# lab2_larionov_buck.net
KiCad netlist of a schematic drawn in Altium Designer
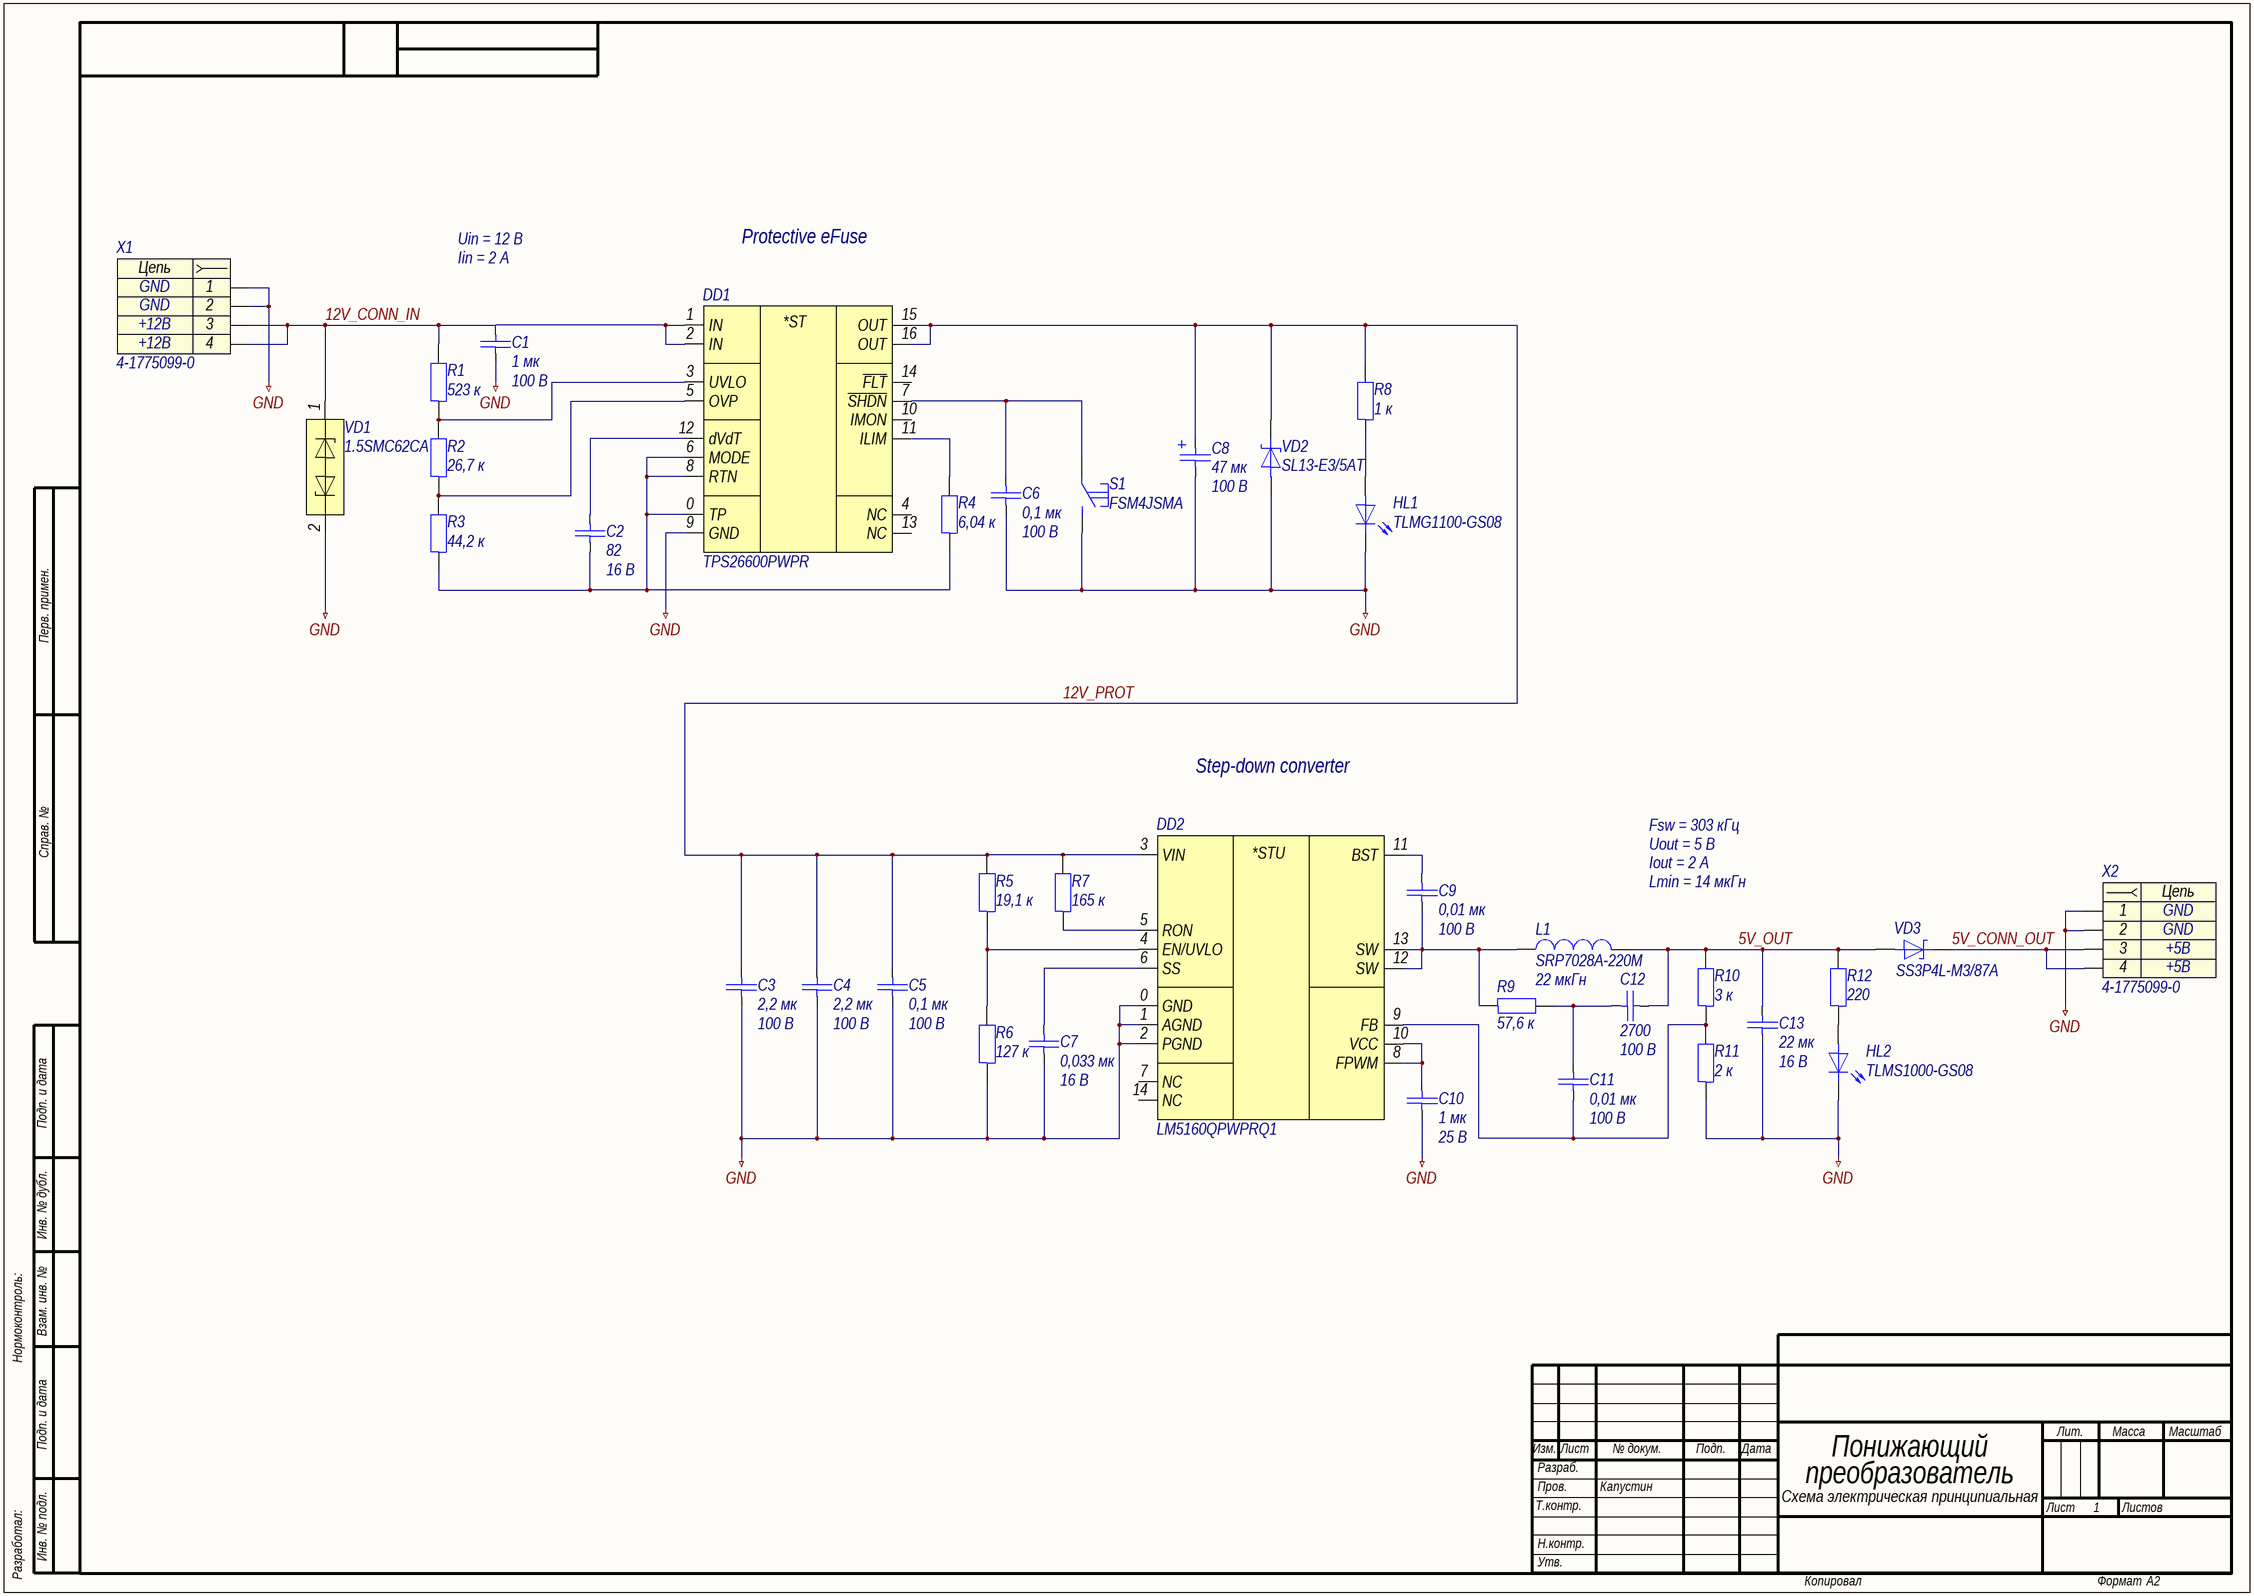
[diagram p0: lab2_larionov_buck.SchDoc]

(export (version "E")
  (design (tool "Eeschema 10.0.6"))
  (components
    (comp (ref "C1")
      (value "1 мк")
      (footprint "C1206")
      (description "=Описание")
      (fields (field (name "НАПРЯЖЕНИЕ") "100 В"))
      (libsource (lib "Database_Students") (part "C-NONPOLAR"))
    )
    (comp (ref "C2")
      (value "82")
      (footprint "C0603")
      (description "=Описание")
      (fields (field (name "НАПРЯЖЕНИЕ") "16 В"))
      (libsource (lib "Database_Students") (part "C-NONPOLAR"))
    )
    (comp (ref "C3")
      (value "2,2 мк")
      (footprint "C1206")
      (description "=Описание")
      (fields (field (name "НАПРЯЖЕНИЕ") "100 В"))
      (libsource (lib "Database_Students") (part "C-NONPOLAR"))
    )
    (comp (ref "C4")
      (value "2,2 мк")
      (footprint "C1206")
      (description "=Описание")
      (fields (field (name "НАПРЯЖЕНИЕ") "100 В"))
      (libsource (lib "Database_Students") (part "C-NONPOLAR"))
    )
    (comp (ref "C5")
      (value "0,1 мк")
      (footprint "C0603")
      (description "=Описание")
      (fields (field (name "НАПРЯЖЕНИЕ") "100 В"))
      (libsource (lib "Database_Students") (part "C-NONPOLAR"))
    )
    (comp (ref "C6")
      (value "0,1 мк")
      (footprint "C0603")
      (description "=Описание")
      (fields (field (name "НАПРЯЖЕНИЕ") "100 В"))
      (libsource (lib "Database_Students") (part "C-NONPOLAR"))
    )
    (comp (ref "C7")
      (value "0,033 мк")
      (footprint "C0603")
      (description "=Описание")
      (fields (field (name "НАПРЯЖЕНИЕ") "16 В"))
      (libsource (lib "Database_Students") (part "C-NONPOLAR"))
    )
    (comp (ref "C8")
      (value "47 мк")
      (footprint "CAPAE-1000X1000X1200")
      (description "=Описание")
      (fields (field (name "НАПРЯЖЕНИЕ") "100 В"))
      (libsource (lib "Database_Students") (part "C-POLAR"))
    )
    (comp (ref "C9")
      (value "0,01 мк")
      (footprint "C0603")
      (description "=Описание")
      (fields (field (name "НАПРЯЖЕНИЕ") "100 В"))
      (libsource (lib "Database_Students") (part "C-NONPOLAR"))
    )
    (comp (ref "C10")
      (value "1 мк")
      (footprint "C0603")
      (description "=Описание")
      (fields (field (name "НАПРЯЖЕНИЕ") "25 В"))
      (libsource (lib "Database_Students") (part "C-NONPOLAR"))
    )
    (comp (ref "C11")
      (value "0,01 мк")
      (footprint "C0603")
      (description "=Описание")
      (fields (field (name "НАПРЯЖЕНИЕ") "100 В"))
      (libsource (lib "Database_Students") (part "C-NONPOLAR"))
    )
    (comp (ref "C12")
      (value "2700")
      (footprint "C0603")
      (description "=Описание")
      (fields (field (name "НАПРЯЖЕНИЕ") "100 В"))
      (libsource (lib "Database_Students") (part "C-NONPOLAR"))
    )
    (comp (ref "C13")
      (value "22 мк")
      (footprint "C1206")
      (description "=Описание")
      (fields (field (name "НАПРЯЖЕНИЕ") "16 В"))
      (libsource (lib "Database_Students") (part "C-NONPOLAR"))
    )
    (comp (ref "DD1")
      (value "TPS26600PWPR")
      (footprint "HTSSOP-16")
      (description "=Описание")
      (libsource (lib "Database_Students") (part "TPS26600PWPR"))
    )
    (comp (ref "DD2")
      (value "LM5160QPWPRQ1")
      (footprint "HTSSOP-14")
      (description "=Описание")
      (libsource (lib "Database_Students") (part "LM5160QPWPRQ1"))
    )
    (comp (ref "HL1")
      (value "TLMG1100-GS08")
      (footprint "HL0603")
      (description "=Описание")
      (libsource (lib "Database_Students") (part "HL-COMMON"))
    )
    (comp (ref "HL2")
      (value "TLMS1000-GS08")
      (footprint "HL0603")
      (description "=Описание")
      (libsource (lib "Database_Students") (part "HL-COMMON"))
    )
    (comp (ref "L1")
      (value "SRP7028A-220M")
      (footprint "SRP-2-670X660X280")
      (description "=Описание")
      (fields (field (name "ИНДУКТИВНОСТЬ") "22 мкГн"))
      (libsource (lib "Database_Students") (part "INDUCTOR-COMMON"))
    )
    (comp (ref "R1")
      (value "523 к")
      (footprint "R0603")
      (description "=Описание")
      (libsource (lib "Database_Students") (part "R-COMMON"))
    )
    (comp (ref "R2")
      (value "26,7 к")
      (footprint "R0603")
      (description "=Описание")
      (libsource (lib "Database_Students") (part "R-COMMON"))
    )
    (comp (ref "R3")
      (value "44,2 к")
      (footprint "R0603")
      (description "=Описание")
      (libsource (lib "Database_Students") (part "R-COMMON"))
    )
    (comp (ref "R4")
      (value "6,04 к")
      (footprint "R0603")
      (description "=Описание")
      (libsource (lib "Database_Students") (part "R-COMMON"))
    )
    (comp (ref "R5")
      (value "19,1 к")
      (footprint "R0603")
      (description "=Описание")
      (libsource (lib "Database_Students") (part "R-COMMON"))
    )
    (comp (ref "R6")
      (value "127 к")
      (footprint "R0603")
      (description "=Описание")
      (libsource (lib "Database_Students") (part "R-COMMON"))
    )
    (comp (ref "R7")
      (value "165 к")
      (footprint "R0603")
      (description "=Описание")
      (libsource (lib "Database_Students") (part "R-COMMON"))
    )
    (comp (ref "R8")
      (value "1 к")
      (footprint "R1218")
      (description "=Описание")
      (libsource (lib "Database_Students") (part "R-COMMON"))
    )
    (comp (ref "R9")
      (value "57,6 к")
      (footprint "R0603")
      (description "=Описание")
      (libsource (lib "Database_Students") (part "R-COMMON"))
    )
    (comp (ref "R10")
      (value "3 к")
      (footprint "R0603")
      (description "=Описание")
      (libsource (lib "Database_Students") (part "R-COMMON"))
    )
    (comp (ref "R11")
      (value "2 к")
      (footprint "R0603")
      (description "=Описание")
      (libsource (lib "Database_Students") (part "R-COMMON"))
    )
    (comp (ref "R12")
      (value "220")
      (footprint "R0603")
      (description "=Описание")
      (libsource (lib "Database_Students") (part "R-COMMON"))
    )
    (comp (ref "S1")
      (value "FSM4JSMA")
      (footprint "FSM4JSMA")
      (description "=Описание")
      (libsource (lib "Database_Students") (part "SWITCH-01"))
    )
    (comp (ref "VD1")
      (value "1.5SMC62CA")
      (footprint "DO-214AB")
      (description "=Описание")
      (libsource (lib "Database_Students") (part "ZENER-BI-DIRECTIONAL"))
    )
    (comp (ref "VD2")
      (value "SL13-E3/5AT")
      (footprint "DO-214AC")
      (description "=Описание")
      (libsource (lib "Database_Students") (part "DIODE-SCHOTTKY"))
    )
    (comp (ref "VD3")
      (value "SS3P4L-M3/87A")
      (footprint "TO-277A")
      (description "=Описание")
      (libsource (lib "Database_Students") (part "DIODE-SCHOTTKY"))
    )
    (comp (ref "X1")
      (value "4-1775099-0")
      (footprint "4-1775099-0")
      (description "=Описание")
      (libsource (lib "Database_Students") (part "HEADER-4-SCT"))
    )
    (comp (ref "X2")
      (value "4-1775099-0")
      (footprint "4-1775099-0")
      (description "=Описание")
      (libsource (lib "") (part "HEADER-4-SCT_1"))
    )
  )
  (nets
    (net (code "1") (name "/5V_CONN_OUT") (class "Default")
      (node (ref "VD3") (pin "1") (pinfunction "1_1") (pintype "passive"))
      (node (ref "X2") (pin "3") (pinfunction "3_3") (pintype "passive"))
      (node (ref "X2") (pin "4") (pinfunction "4_4") (pintype "passive"))
    )
    (net (code "2") (name "/5V_OUT") (class "Default")
      (node (ref "C12") (pin "1") (pinfunction "1_1") (pintype "passive"))
      (node (ref "C13") (pin "1") (pinfunction "1_1") (pintype "passive"))
      (node (ref "L1") (pin "2") (pinfunction "2_2") (pintype "passive"))
      (node (ref "R10") (pin "2") (pinfunction "2_2") (pintype "passive"))
      (node (ref "R12") (pin "2") (pinfunction "2_2") (pintype "passive"))
      (node (ref "VD3") (pin "2") (pinfunction "2_2") (pintype "passive"))
    )
    (net (code "3") (name "/12V_CONN_IN") (class "Default")
      (node (ref "C1") (pin "1") (pinfunction "1_1") (pintype "passive"))
      (node (ref "DD1") (pin "1") (pinfunction "IN_1") (pintype "passive"))
      (node (ref "DD1") (pin "2") (pinfunction "IN_2") (pintype "passive"))
      (node (ref "R1") (pin "2") (pinfunction "2_2") (pintype "passive"))
      (node (ref "VD1") (pin "1") (pinfunction "1_1") (pintype "passive"))
      (node (ref "X1") (pin "3") (pinfunction "3_3") (pintype "passive"))
      (node (ref "X1") (pin "4") (pinfunction "4_4") (pintype "passive"))
    )
    (net (code "4") (name "/12V_PROT") (class "Default")
      (node (ref "C3") (pin "1") (pinfunction "1_1") (pintype "passive"))
      (node (ref "C4") (pin "1") (pinfunction "1_1") (pintype "passive"))
      (node (ref "C5") (pin "1") (pinfunction "1_1") (pintype "passive"))
      (node (ref "C8") (pin "1") (pinfunction "1_1") (pintype "passive"))
      (node (ref "DD1") (pin "15") (pinfunction "OUT_15") (pintype "passive"))
      (node (ref "DD1") (pin "16") (pinfunction "OUT_16") (pintype "passive"))
      (node (ref "DD2") (pin "3") (pinfunction "VIN_3") (pintype "passive"))
      (node (ref "R5") (pin "2") (pinfunction "2_2") (pintype "passive"))
      (node (ref "R7") (pin "2") (pinfunction "2_2") (pintype "passive"))
      (node (ref "R8") (pin "2") (pinfunction "2_2") (pintype "passive"))
      (node (ref "VD2") (pin "1") (pinfunction "1_1") (pintype "passive"))
    )
    (net (code "5") (name "GND") (class "Default")
      (node (ref "C1") (pin "2") (pinfunction "2_2") (pintype "passive"))
      (node (ref "C10") (pin "2") (pinfunction "2_2") (pintype "passive"))
      (node (ref "C13") (pin "2") (pinfunction "2_2") (pintype "passive"))
      (node (ref "C3") (pin "2") (pinfunction "2_2") (pintype "passive"))
      (node (ref "C4") (pin "2") (pinfunction "2_2") (pintype "passive"))
      (node (ref "C5") (pin "2") (pinfunction "2_2") (pintype "passive"))
      (node (ref "C6") (pin "2") (pinfunction "2_2") (pintype "passive"))
      (node (ref "C7") (pin "2") (pinfunction "2_2") (pintype "passive"))
      (node (ref "C8") (pin "2") (pinfunction "2_2") (pintype "passive"))
      (node (ref "DD1") (pin "9") (pinfunction "GND_9") (pintype "passive"))
      (node (ref "DD2") (pin "0") (pinfunction "GND_0") (pintype "passive"))
      (node (ref "DD2") (pin "1") (pinfunction "AGND_1") (pintype "passive"))
      (node (ref "DD2") (pin "2") (pinfunction "PGND_2") (pintype "passive"))
      (node (ref "HL1") (pin "1") (pinfunction "1_1") (pintype "passive"))
      (node (ref "HL2") (pin "1") (pinfunction "1_1") (pintype "passive"))
      (node (ref "R11") (pin "1") (pinfunction "1_1") (pintype "passive"))
      (node (ref "R6") (pin "1") (pinfunction "1_1") (pintype "passive"))
      (node (ref "S1") (pin "2") (pinfunction "2_2") (pintype "passive"))
      (node (ref "VD1") (pin "2") (pinfunction "2_2") (pintype "passive"))
      (node (ref "VD2") (pin "2") (pinfunction "2_2") (pintype "passive"))
      (node (ref "X1") (pin "1") (pinfunction "1_1") (pintype "passive"))
      (node (ref "X1") (pin "2") (pinfunction "2_2") (pintype "passive"))
      (node (ref "X2") (pin "1") (pinfunction "1_1") (pintype "passive"))
      (node (ref "X2") (pin "2") (pinfunction "2_2") (pintype "passive"))
    )
    (net (code "6") (name "Net-(C9-Pad2)") (class "Default")
      (node (ref "C9") (pin "2") (pinfunction "2_2") (pintype "passive"))
      (node (ref "DD2") (pin "12") (pinfunction "SW_12") (pintype "passive"))
      (node (ref "DD2") (pin "13") (pinfunction "SW_13") (pintype "passive"))
      (node (ref "L1") (pin "1") (pinfunction "1_1") (pintype "passive"))
      (node (ref "R9") (pin "1") (pinfunction "1_1") (pintype "passive"))
    )
    (net (code "7") (name "Net-(C11-Pad1)") (class "Default")
      (node (ref "C11") (pin "1") (pinfunction "1_1") (pintype "passive"))
      (node (ref "C12") (pin "2") (pinfunction "2_2") (pintype "passive"))
      (node (ref "R9") (pin "2") (pinfunction "2_2") (pintype "passive"))
    )
    (net (code "8") (name "Net-(DD1-ILIM)") (class "Default")
      (node (ref "DD1") (pin "11") (pinfunction "ILIM_11") (pintype "passive"))
      (node (ref "R4") (pin "2") (pinfunction "2_2") (pintype "passive"))
    )
    (net (code "9") (name "Net-(DD1-MODE)") (class "Default")
      (node (ref "C2") (pin "2") (pinfunction "2_2") (pintype "passive"))
      (node (ref "DD1") (pin "0") (pinfunction "TP_0") (pintype "passive"))
      (node (ref "DD1") (pin "6") (pinfunction "MODE_6") (pintype "passive"))
      (node (ref "DD1") (pin "8") (pinfunction "RTN_8") (pintype "passive"))
      (node (ref "R3") (pin "1") (pinfunction "1_1") (pintype "passive"))
      (node (ref "R4") (pin "1") (pinfunction "1_1") (pintype "passive"))
    )
    (net (code "10") (name "Net-(DD1-OVP)") (class "Default")
      (node (ref "DD1") (pin "5") (pinfunction "OVP_5") (pintype "passive"))
      (node (ref "R2") (pin "1") (pinfunction "1_1") (pintype "passive"))
      (node (ref "R3") (pin "2") (pinfunction "2_2") (pintype "passive"))
    )
    (net (code "11") (name "Net-(DD1-UVLO)") (class "Default")
      (node (ref "DD1") (pin "3") (pinfunction "UVLO_3") (pintype "passive"))
      (node (ref "R1") (pin "1") (pinfunction "1_1") (pintype "passive"))
      (node (ref "R2") (pin "2") (pinfunction "2_2") (pintype "passive"))
    )
    (net (code "12") (name "Net-(DD1-dVdT)") (class "Default")
      (node (ref "C2") (pin "1") (pinfunction "1_1") (pintype "passive"))
      (node (ref "DD1") (pin "12") (pinfunction "dVdT_12") (pintype "passive"))
    )
    (net (code "13") (name "Net-(DD1-~{SHDN})") (class "Default")
      (node (ref "C6") (pin "1") (pinfunction "1_1") (pintype "passive"))
      (node (ref "DD1") (pin "7") (pinfunction "~{SHDN}_7") (pintype "passive"))
      (node (ref "S1") (pin "1") (pinfunction "1_1") (pintype "passive"))
    )
    (net (code "14") (name "Net-(DD2-BST)") (class "Default")
      (node (ref "C9") (pin "1") (pinfunction "1_1") (pintype "passive"))
      (node (ref "DD2") (pin "11") (pinfunction "BST_11") (pintype "passive"))
    )
    (net (code "15") (name "Net-(DD2-EN{slash}UVLO)") (class "Default")
      (node (ref "DD2") (pin "4") (pinfunction "EN/UVLO_4") (pintype "passive"))
      (node (ref "R5") (pin "1") (pinfunction "1_1") (pintype "passive"))
      (node (ref "R6") (pin "2") (pinfunction "2_2") (pintype "passive"))
    )
    (net (code "16") (name "Net-(DD2-FB)") (class "Default")
      (node (ref "C11") (pin "2") (pinfunction "2_2") (pintype "passive"))
      (node (ref "DD2") (pin "9") (pinfunction "FB_9") (pintype "passive"))
      (node (ref "R10") (pin "1") (pinfunction "1_1") (pintype "passive"))
      (node (ref "R11") (pin "2") (pinfunction "2_2") (pintype "passive"))
    )
    (net (code "17") (name "Net-(DD2-FPWM)") (class "Default")
      (node (ref "C10") (pin "1") (pinfunction "1_1") (pintype "passive"))
      (node (ref "DD2") (pin "10") (pinfunction "VCC_10") (pintype "passive"))
      (node (ref "DD2") (pin "8") (pinfunction "FPWM_8") (pintype "passive"))
    )
    (net (code "18") (name "Net-(DD2-RON)") (class "Default")
      (node (ref "DD2") (pin "5") (pinfunction "RON_5") (pintype "passive"))
      (node (ref "R7") (pin "1") (pinfunction "1_1") (pintype "passive"))
    )
    (net (code "19") (name "Net-(DD2-SS)") (class "Default")
      (node (ref "C7") (pin "1") (pinfunction "1_1") (pintype "passive"))
      (node (ref "DD2") (pin "6") (pinfunction "SS_6") (pintype "passive"))
    )
    (net (code "20") (name "Net-(HL1-Pad2)") (class "Default")
      (node (ref "HL1") (pin "2") (pinfunction "2_2") (pintype "passive"))
      (node (ref "R8") (pin "1") (pinfunction "1_1") (pintype "passive"))
    )
    (net (code "21") (name "Net-(HL2-Pad2)") (class "Default")
      (node (ref "HL2") (pin "2") (pinfunction "2_2") (pintype "passive"))
      (node (ref "R12") (pin "1") (pinfunction "1_1") (pintype "passive"))
    )
    (net (code "22") (name "unconnected-(DD1-IMON-Pad10)") (class "Default")
      (node (ref "DD1") (pin "10") (pinfunction "IMON_10") (pintype "passive"))
    )
    (net (code "23") (name "unconnected-(DD1-NC-Pad4)") (class "Default")
      (node (ref "DD1") (pin "4") (pinfunction "NC_4") (pintype "passive"))
    )
    (net (code "24") (name "unconnected-(DD1-NC-Pad13)") (class "Default")
      (node (ref "DD1") (pin "13") (pinfunction "NC_13") (pintype "passive"))
    )
    (net (code "25") (name "unconnected-(DD1-~{FLT}-Pad14)") (class "Default")
      (node (ref "DD1") (pin "14") (pinfunction "~{FLT}_14") (pintype "passive"))
    )
    (net (code "26") (name "unconnected-(DD2-NC-Pad7)") (class "Default")
      (node (ref "DD2") (pin "7") (pinfunction "NC_7") (pintype "passive"))
    )
    (net (code "27") (name "unconnected-(DD2-NC-Pad14)") (class "Default")
      (node (ref "DD2") (pin "14") (pinfunction "NC_14") (pintype "passive"))
    )
  )
)
